# main.net
KiCad netlist of a schematic drawn in Altium Designer
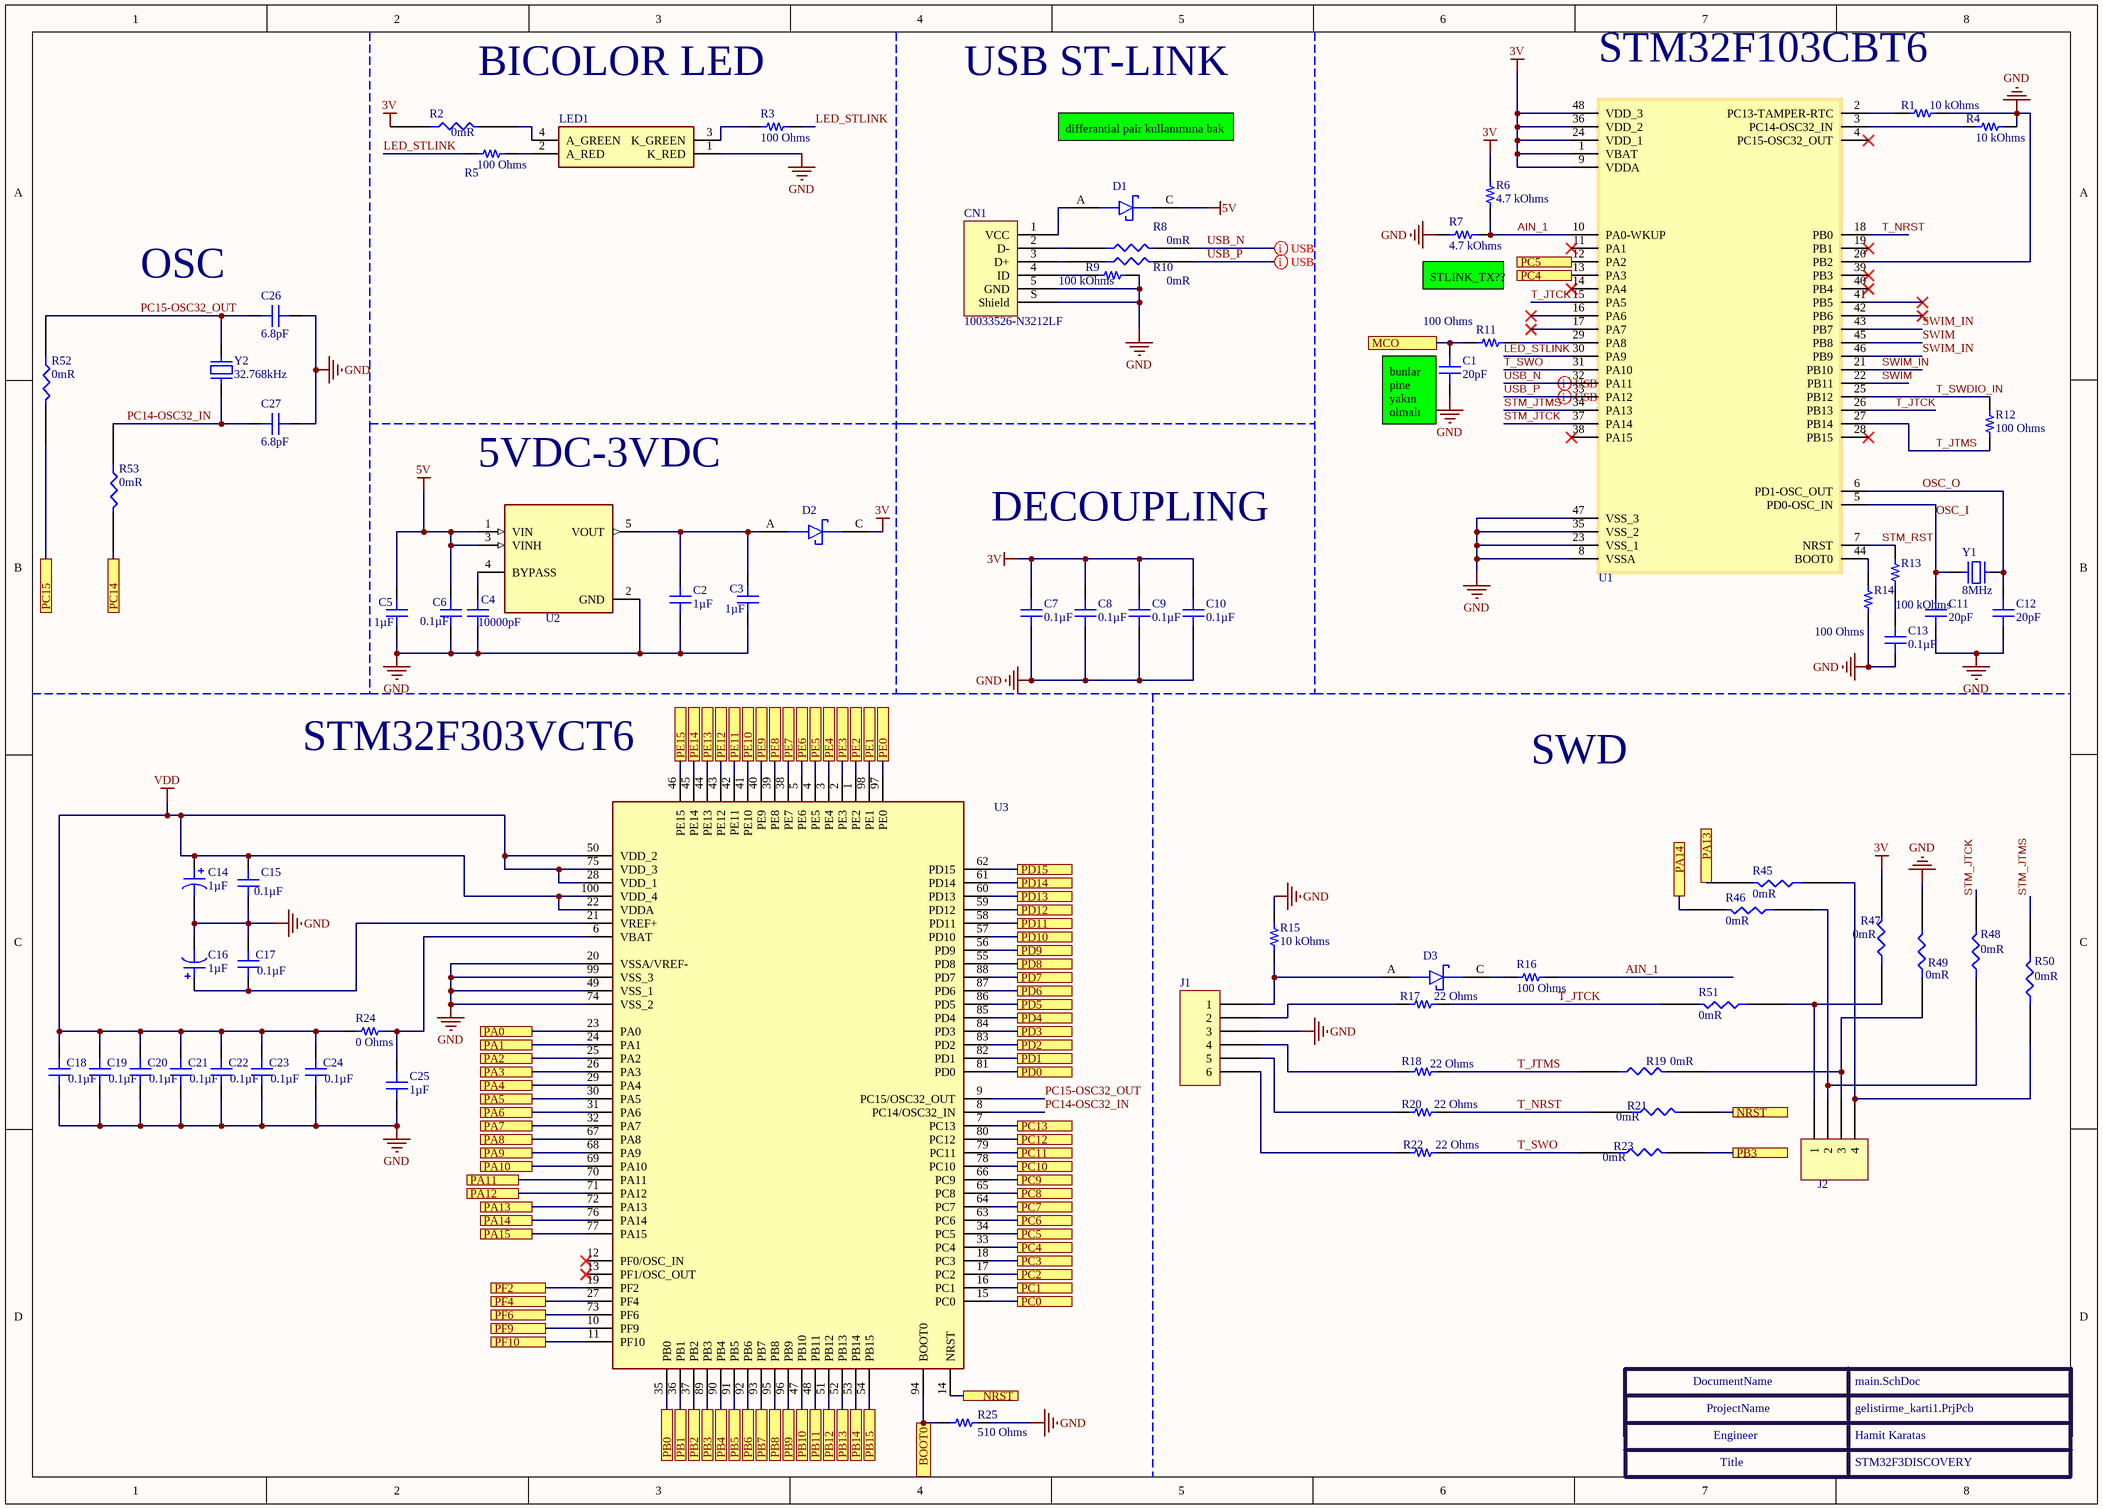
[diagram p0: main.SchDoc]

(export (version "E")
  (design (tool "Eeschema 10.0.6"))
  (components
    (comp (ref "C1")
      (value "20pF")
      (footprint "CAP 0603_1608")
      (description "CAP CER 20PF 250V 0603")
      (fields (field (name "PART NUMBER") "SQCSVA200JAT1A") (field (name "MANUFACTURER") "AVX Corporation"))
      (libsource (lib "Celestial Altium Library - altium_library (4)") (part "Capacitor"))
    )
    (comp (ref "C2")
      (value "1µF")
      (footprint "CAP 0603_1608")
      (description "CAP CER 0603 1UF 16V X7R 10%")
      (fields (field (name "PART NUMBER") "C0603C105K4RACAUTO") (field (name "MANUFACTURER") "KEMET"))
      (libsource (lib "Celestial Altium Library - altium_library (4)") (part "Capacitor"))
    )
    (comp (ref "C3")
      (value "1µF")
      (footprint "CAP 0603_1608")
      (description "CAP CER 0603 1UF 16V X7R 10%")
      (fields (field (name "PART NUMBER") "C0603C105K4RACAUTO") (field (name "MANUFACTURER") "KEMET"))
      (libsource (lib "Celestial Altium Library - altium_library (4)") (part "Capacitor"))
    )
    (comp (ref "C4")
      (value "10000pF")
      (footprint "CAP 0603_1608")
      (description "CAP CER 0603 10NF 100V X7R")
      (fields (field (name "PART NUMBER") "C0603X103K1RAC3316") (field (name "MANUFACTURER") "KEMET"))
      (libsource (lib "Celestial Altium Library - altium_library (4)") (part "Capacitor"))
    )
    (comp (ref "C5")
      (value "1µF")
      (footprint "CAP 0603_1608")
      (description "CAP CER 0603 1UF 16V X7R 10%")
      (fields (field (name "PART NUMBER") "C0603C105K4RACAUTO") (field (name "MANUFACTURER") "KEMET"))
      (libsource (lib "Celestial Altium Library - altium_library (4)") (part "Capacitor"))
    )
    (comp (ref "C6")
      (value "0.1µF")
      (footprint "CAP 0603_1608")
      (description "CAP CER 0.1UF 50V X7R 0603")
      (fields (field (name "PART NUMBER") "C0603C104K5RAC7411") (field (name "MANUFACTURER") "KEMET"))
      (libsource (lib "Celestial Altium Library - altium_library (4)") (part "Capacitor"))
    )
    (comp (ref "C7")
      (value "0.1µF")
      (footprint "CAP 0603_1608")
      (description "CAP CER 0.1UF 50V X7R 0603")
      (fields (field (name "PART NUMBER") "C0603C104K5RAC7411") (field (name "MANUFACTURER") "KEMET"))
      (libsource (lib "Celestial Altium Library - altium_library (4)") (part "Capacitor"))
    )
    (comp (ref "C8")
      (value "0.1µF")
      (footprint "CAP 0603_1608")
      (description "CAP CER 0.1UF 50V X7R 0603")
      (fields (field (name "PART NUMBER") "C0603C104K5RAC7411") (field (name "MANUFACTURER") "KEMET"))
      (libsource (lib "Celestial Altium Library - altium_library (4)") (part "Capacitor"))
    )
    (comp (ref "C9")
      (value "0.1µF")
      (footprint "CAP 0603_1608")
      (description "CAP CER 0.1UF 50V X7R 0603")
      (fields (field (name "PART NUMBER") "C0603C104K5RAC7411") (field (name "MANUFACTURER") "KEMET"))
      (libsource (lib "Celestial Altium Library - altium_library (4)") (part "Capacitor"))
    )
    (comp (ref "C10")
      (value "0.1µF")
      (footprint "CAP 0603_1608")
      (description "CAP CER 0.1UF 50V X7R 0603")
      (fields (field (name "PART NUMBER") "C0603C104K5RAC7411") (field (name "MANUFACTURER") "KEMET"))
      (libsource (lib "Celestial Altium Library - altium_library (4)") (part "Capacitor"))
    )
    (comp (ref "C11")
      (value "20pF")
      (footprint "CAP 0603_1608")
      (description "CAP CER 20PF 250V 0603")
      (fields (field (name "PART NUMBER") "SQCSVA200JAT1A") (field (name "MANUFACTURER") "AVX Corporation"))
      (libsource (lib "Celestial Altium Library - altium_library (4)") (part "Capacitor"))
    )
    (comp (ref "C12")
      (value "20pF")
      (footprint "CAP 0603_1608")
      (description "CAP CER 20PF 250V 0603")
      (fields (field (name "PART NUMBER") "SQCSVA200JAT1A") (field (name "MANUFACTURER") "AVX Corporation"))
      (libsource (lib "Celestial Altium Library - altium_library (4)") (part "Capacitor"))
    )
    (comp (ref "C13")
      (value "0.1µF")
      (footprint "CAP 0603_1608")
      (description "CAP CER 0.1UF 50V X7R 0603")
      (fields (field (name "PART NUMBER") "C0603C104K5RAC7411") (field (name "MANUFACTURER") "KEMET"))
      (libsource (lib "Celestial Altium Library - altium_library (4)") (part "Capacitor"))
    )
    (comp (ref "C14")
      (value "1µF")
      (footprint "CAP ALSMD POLY 4.3MM H5.5MM")
      (description "CAP ALUM 1UF 20% 50V SMD")
      (fields
        (field (name "PART NUMBER") "EEE-1HA010NR")
        (field (name "MANUFACTURER") "Panasonic Electronic Components")
      )
      (libsource (lib "Celestial Altium Library - altium_library (4)") (part "Polarised Capacitor"))
    )
    (comp (ref "C15")
      (value "0.1µF")
      (footprint "CAP 0603_1608")
      (description "CAP CER 0.1UF 50V X7R 0603")
      (fields (field (name "PART NUMBER") "C0603C104K5RAC7411") (field (name "MANUFACTURER") "KEMET"))
      (libsource (lib "Celestial Altium Library - altium_library (4)") (part "Capacitor"))
    )
    (comp (ref "C16")
      (value "1µF")
      (footprint "CAP ALSMD POLY 4.3MM H5.5MM")
      (description "CAP ALUM 1UF 20% 50V SMD")
      (fields
        (field (name "PART NUMBER") "EEE-1HA010NR")
        (field (name "MANUFACTURER") "Panasonic Electronic Components")
      )
      (libsource (lib "Celestial Altium Library - altium_library (4)") (part "Polarised Capacitor"))
    )
    (comp (ref "C17")
      (value "0.1µF")
      (footprint "CAP 0603_1608")
      (description "CAP CER 0.1UF 50V X7R 0603")
      (fields (field (name "PART NUMBER") "C0603C104K5RAC7411") (field (name "MANUFACTURER") "KEMET"))
      (libsource (lib "Celestial Altium Library - altium_library (4)") (part "Capacitor"))
    )
    (comp (ref "C18")
      (value "0.1µF")
      (footprint "CAP 0603_1608")
      (description "CAP CER 0.1UF 50V X7R 0603")
      (fields (field (name "PART NUMBER") "C0603C104K5RAC7411") (field (name "MANUFACTURER") "KEMET"))
      (libsource (lib "Celestial Altium Library - altium_library (4)") (part "Capacitor"))
    )
    (comp (ref "C19")
      (value "0.1µF")
      (footprint "CAP 0603_1608")
      (description "CAP CER 0.1UF 50V X7R 0603")
      (fields (field (name "PART NUMBER") "C0603C104K5RAC7411") (field (name "MANUFACTURER") "KEMET"))
      (libsource (lib "Celestial Altium Library - altium_library (4)") (part "Capacitor"))
    )
    (comp (ref "C20")
      (value "0.1µF")
      (footprint "CAP 0603_1608")
      (description "CAP CER 0.1UF 50V X7R 0603")
      (fields (field (name "PART NUMBER") "C0603C104K5RAC7411") (field (name "MANUFACTURER") "KEMET"))
      (libsource (lib "Celestial Altium Library - altium_library (4)") (part "Capacitor"))
    )
    (comp (ref "C21")
      (value "0.1µF")
      (footprint "CAP 0603_1608")
      (description "CAP CER 0.1UF 50V X7R 0603")
      (fields (field (name "PART NUMBER") "C0603C104K5RAC7411") (field (name "MANUFACTURER") "KEMET"))
      (libsource (lib "Celestial Altium Library - altium_library (4)") (part "Capacitor"))
    )
    (comp (ref "C22")
      (value "0.1µF")
      (footprint "CAP 0603_1608")
      (description "CAP CER 0.1UF 50V X7R 0603")
      (fields (field (name "PART NUMBER") "C0603C104K5RAC7411") (field (name "MANUFACTURER") "KEMET"))
      (libsource (lib "Celestial Altium Library - altium_library (4)") (part "Capacitor"))
    )
    (comp (ref "C23")
      (value "0.1µF")
      (footprint "CAP 0603_1608")
      (description "CAP CER 0.1UF 50V X7R 0603")
      (fields (field (name "PART NUMBER") "C0603C104K5RAC7411") (field (name "MANUFACTURER") "KEMET"))
      (libsource (lib "Celestial Altium Library - altium_library (4)") (part "Capacitor"))
    )
    (comp (ref "C24")
      (value "0.1µF")
      (footprint "CAP 0603_1608")
      (description "CAP CER 0.1UF 50V X7R 0603")
      (fields (field (name "PART NUMBER") "C0603C104K5RAC7411") (field (name "MANUFACTURER") "KEMET"))
      (libsource (lib "Celestial Altium Library - altium_library (4)") (part "Capacitor"))
    )
    (comp (ref "C25")
      (value "1µF")
      (footprint "CAP 0603_1608")
      (description "CAP CER 0603 1UF 16V X7R 10%")
      (fields (field (name "PART NUMBER") "C0603C105K4RACAUTO") (field (name "MANUFACTURER") "KEMET"))
      (libsource (lib "Celestial Altium Library - altium_library (4)") (part "Capacitor"))
    )
    (comp (ref "C26")
      (value "6.8pF")
      (footprint "CAP 0603_1608")
      (description "CAP CER 6.8PF 50V C0G/NP0 0603")
      (fields (field (name "PART NUMBER") "C0603C689J5GACTU") (field (name "MANUFACTURER") "KEMET"))
      (libsource (lib "Celestial Altium Library - altium_library (4)") (part "Capacitor"))
    )
    (comp (ref "C27")
      (value "6.8pF")
      (footprint "CAP 0603_1608")
      (description "CAP CER 6.8PF 50V C0G/NP0 0603")
      (fields (field (name "PART NUMBER") "C0603C689J5GACTU") (field (name "MANUFACTURER") "KEMET"))
      (libsource (lib "Celestial Altium Library - altium_library (4)") (part "Capacitor"))
    )
    (comp (ref "CN1")
      (value "10033526-N3212LF")
      (footprint "FCI USB 10033526-N3212LF")
      (description "CONN RCPT MINI USB B 5POS SMD RA")
      (fields (field (name "MANUFACTURER") "Amphenol ICC (FCI)"))
      (libsource (lib "Celestial Altium Library - altium_library (4)") (part "USB 2.0 Type B Micro"))
    )
    (comp (ref "D1")
      (value "BAT60J")
      (footprint "SOD-323")
      (fields
        (field (name "MANUFACTURER") "STMicroelectronics")
        (field (name "MANUFACTURER PART NUMBER") "BAT60JFILM")
      )
      (libsource (lib "giris_intlib") (part "DIODE SCHOTTKY"))
    )
    (comp (ref "D2")
      (value "BAT60J")
      (footprint "SOD-323")
      (fields
        (field (name "MANUFACTURER") "STMicroelectronics")
        (field (name "MANUFACTURER PART NUMBER") "BAT60JFILM")
      )
      (libsource (lib "giris_intlib") (part "DIODE SCHOTTKY"))
    )
    (comp (ref "D3")
      (value "BAT60J")
      (footprint "SOD-323")
      (fields
        (field (name "MANUFACTURER") "STMicroelectronics")
        (field (name "MANUFACTURER PART NUMBER") "BAT60JFILM")
      )
      (libsource (lib "giris_intlib") (part "DIODE SCHOTTKY"))
    )
    (comp (ref "J1")
      (value "B6B-PH-K(LF)(SN)")
      (footprint "JST B6B-PH-K")
      (description "CONN HEADER VERT 6POS 2MM")
      (fields (field (name "MANUFACTURER") "JST Sales America Inc."))
      (libsource (lib "Celestial Altium Library - altium_library (4)") (part "6 Pin"))
    )
    (comp (ref "J2")
      (value "B4B-PH-K-S(LF)(SN)")
      (footprint "JST B4B-PH-K")
      (description "CONN HEADER VERT 4POS 2MM")
      (fields (field (name "MANUFACTURER") "JST Sales America Inc."))
      (libsource (lib "Celestial Altium Library - altium_library (4)") (part "4 Pin"))
    )
    (comp (ref "LED1")
      (value "IN-S85DATRG")
      (footprint "altium_giris:INS85DATRG")
      (description "LED")
      (fields (field (name "MOUSER PART NUMBER") "743-IN-S85DATRG"))
      (libsource (lib "*") (part "IN-S85DATRG"))
    )
    (comp (ref "R1")
      (value "10 kOhms")
      (footprint "RES 0603_1608")
      (description "RES SMD 10K OHM 0.5% 1/10W 0603")
      (fields (field (name "PART NUMBER") "RT0603DRD0710KL") (field (name "MANUFACTURER") "Yageo"))
      (libsource (lib "Celestial Altium Library - altium_library (4)") (part "Resistor"))
    )
    (comp (ref "R2")
      (value "RC0603JR-070RL")
      (footprint "RES_0603")
      (description "RES SMD 0 OHM JUMPER 1/10W 0603")
      (fields
        (field (name "MANUFACTURER") "Yageo")
        (field (name "TOLERANCE") "1%")
        (field (name "RESISTANCE") "0mR")
      )
      (libsource (lib "giris_intlib") (part "Res 0 ohm 0603"))
    )
    (comp (ref "R3")
      (value "100 Ohms")
      (footprint "RES 0603_1608")
      (description "RES 100 OHM 0.1% 1/16W 0603")
      (fields
        (field (name "PART NUMBER") "RNCS0603BKE100R")
        (field (name "MANUFACTURER") "Stackpole Electronics Inc")
      )
      (libsource (lib "Celestial Altium Library - altium_library (4)") (part "Resistor"))
    )
    (comp (ref "R4")
      (value "10 kOhms")
      (footprint "RES 0603_1608")
      (description "RES SMD 10K OHM 0.5% 1/10W 0603")
      (fields (field (name "PART NUMBER") "RT0603DRD0710KL") (field (name "MANUFACTURER") "Yageo"))
      (libsource (lib "Celestial Altium Library - altium_library (4)") (part "Resistor"))
    )
    (comp (ref "R5")
      (value "100 Ohms")
      (footprint "RES 0603_1608")
      (description "RES 100 OHM 0.1% 1/16W 0603")
      (fields
        (field (name "PART NUMBER") "RNCS0603BKE100R")
        (field (name "MANUFACTURER") "Stackpole Electronics Inc")
      )
      (libsource (lib "Celestial Altium Library - altium_library (4)") (part "Resistor"))
    )
    (comp (ref "R6")
      (value "4.7 kOhms")
      (footprint "RES 0603_1608")
      (description "RES SMD 4.7K OHM 1% 1/10W 0603")
      (fields (field (name "PART NUMBER") "RT0603FRE074K7L") (field (name "MANUFACTURER") "Yageo"))
      (libsource (lib "Celestial Altium Library - altium_library (4)") (part "Resistor"))
    )
    (comp (ref "R7")
      (value "4.7 kOhms")
      (footprint "RES 0603_1608")
      (description "RES SMD 4.7K OHM 1% 1/10W 0603")
      (fields (field (name "PART NUMBER") "RT0603FRE074K7L") (field (name "MANUFACTURER") "Yageo"))
      (libsource (lib "Celestial Altium Library - altium_library (4)") (part "Resistor"))
    )
    (comp (ref "R8")
      (value "RC0603JR-070RL")
      (footprint "RES_0603")
      (description "RES SMD 0 OHM JUMPER 1/10W 0603")
      (fields
        (field (name "MANUFACTURER") "Yageo")
        (field (name "TOLERANCE") "1%")
        (field (name "RESISTANCE") "0mR")
      )
      (libsource (lib "giris_intlib") (part "Res 0 ohm 0603"))
    )
    (comp (ref "R9")
      (value "100 kOhms")
      (footprint "RES 0603_1608")
      (description "RES SMD 100K OHM 0.5% 1/10W 0603")
      (fields (field (name "PART NUMBER") "AT0603DRD07100KL") (field (name "MANUFACTURER") "Yageo"))
      (libsource (lib "Celestial Altium Library - altium_library (4)") (part "Resistor"))
    )
    (comp (ref "R10")
      (value "RC0603JR-070RL")
      (footprint "RES_0603")
      (description "RES SMD 0 OHM JUMPER 1/10W 0603")
      (fields
        (field (name "MANUFACTURER") "Yageo")
        (field (name "TOLERANCE") "1%")
        (field (name "RESISTANCE") "0mR")
      )
      (libsource (lib "giris_intlib") (part "Res 0 ohm 0603"))
    )
    (comp (ref "R11")
      (value "100 Ohms")
      (footprint "RES 0603_1608")
      (description "RES 100 OHM 0.1% 1/16W 0603")
      (fields
        (field (name "PART NUMBER") "RNCS0603BKE100R")
        (field (name "MANUFACTURER") "Stackpole Electronics Inc")
      )
      (libsource (lib "Celestial Altium Library - altium_library (4)") (part "Resistor"))
    )
    (comp (ref "R12")
      (value "100 Ohms")
      (footprint "RES 0603_1608")
      (description "RES 100 OHM 0.1% 1/16W 0603")
      (fields
        (field (name "PART NUMBER") "RNCS0603BKE100R")
        (field (name "MANUFACTURER") "Stackpole Electronics Inc")
      )
      (libsource (lib "Celestial Altium Library - altium_library (4)") (part "Resistor"))
    )
    (comp (ref "R13")
      (value "100 kOhms")
      (footprint "RES 0603_1608")
      (description "RES SMD 100K OHM 0.5% 1/10W 0603")
      (fields (field (name "PART NUMBER") "AT0603DRD07100KL") (field (name "MANUFACTURER") "Yageo"))
      (libsource (lib "Celestial Altium Library - altium_library (4)") (part "Resistor"))
    )
    (comp (ref "R14")
      (value "100 Ohms")
      (footprint "RES 0603_1608")
      (description "RES 100 OHM 0.1% 1/16W 0603")
      (fields
        (field (name "PART NUMBER") "RNCS0603BKE100R")
        (field (name "MANUFACTURER") "Stackpole Electronics Inc")
      )
      (libsource (lib "Celestial Altium Library - altium_library (4)") (part "Resistor"))
    )
    (comp (ref "R15")
      (value "10 kOhms")
      (footprint "RES 0603_1608")
      (description "RES SMD 10K OHM 0.5% 1/10W 0603")
      (fields (field (name "PART NUMBER") "RT0603DRD0710KL") (field (name "MANUFACTURER") "Yageo"))
      (libsource (lib "Celestial Altium Library - altium_library (4)") (part "Resistor"))
    )
    (comp (ref "R16")
      (value "100 Ohms")
      (footprint "RES 0603_1608")
      (description "RES 100 OHM 0.1% 1/16W 0603")
      (fields
        (field (name "PART NUMBER") "RNCS0603BKE100R")
        (field (name "MANUFACTURER") "Stackpole Electronics Inc")
      )
      (libsource (lib "Celestial Altium Library - altium_library (4)") (part "Resistor"))
    )
    (comp (ref "R17")
      (value "22 Ohms")
      (footprint "RES 0603_1608")
      (description "RES 22 OHM 5% 1/8W 0603")
      (fields
        (field (name "PART NUMBER") "RK73B1JTTD220J")
        (field (name "MANUFACTURER") "KOA Speer Electronics, Inc.")
      )
      (libsource (lib "Celestial Altium Library - altium_library (4)") (part "Resistor"))
    )
    (comp (ref "R18")
      (value "22 Ohms")
      (footprint "RES 0603_1608")
      (description "RES 22 OHM 5% 1/8W 0603")
      (fields
        (field (name "PART NUMBER") "RK73B1JTTD220J")
        (field (name "MANUFACTURER") "KOA Speer Electronics, Inc.")
      )
      (libsource (lib "Celestial Altium Library - altium_library (4)") (part "Resistor"))
    )
    (comp (ref "R19")
      (value "RC0603JR-070RL")
      (footprint "RES_0603")
      (description "RES SMD 0 OHM JUMPER 1/10W 0603")
      (fields
        (field (name "MANUFACTURER") "Yageo")
        (field (name "TOLERANCE") "1%")
        (field (name "RESISTANCE") "0mR")
      )
      (libsource (lib "giris_intlib") (part "Res 0 ohm 0603"))
    )
    (comp (ref "R20")
      (value "22 Ohms")
      (footprint "RES 0603_1608")
      (description "RES 22 OHM 5% 1/8W 0603")
      (fields
        (field (name "PART NUMBER") "RK73B1JTTD220J")
        (field (name "MANUFACTURER") "KOA Speer Electronics, Inc.")
      )
      (libsource (lib "Celestial Altium Library - altium_library (4)") (part "Resistor"))
    )
    (comp (ref "R21")
      (value "RC0603JR-070RL")
      (footprint "RES_0603")
      (description "RES SMD 0 OHM JUMPER 1/10W 0603")
      (fields
        (field (name "MANUFACTURER") "Yageo")
        (field (name "TOLERANCE") "1%")
        (field (name "RESISTANCE") "0mR")
      )
      (libsource (lib "giris_intlib") (part "Res 0 ohm 0603"))
    )
    (comp (ref "R22")
      (value "22 Ohms")
      (footprint "RES 0603_1608")
      (description "RES 22 OHM 5% 1/8W 0603")
      (fields
        (field (name "PART NUMBER") "RK73B1JTTD220J")
        (field (name "MANUFACTURER") "KOA Speer Electronics, Inc.")
      )
      (libsource (lib "Celestial Altium Library - altium_library (4)") (part "Resistor"))
    )
    (comp (ref "R23")
      (value "RC0603JR-070RL")
      (footprint "RES_0603")
      (description "RES SMD 0 OHM JUMPER 1/10W 0603")
      (fields
        (field (name "MANUFACTURER") "Yageo")
        (field (name "TOLERANCE") "1%")
        (field (name "RESISTANCE") "0mR")
      )
      (libsource (lib "giris_intlib") (part "Res 0 ohm 0603"))
    )
    (comp (ref "R24")
      (value "0 Ohms")
      (footprint "RES 0603_1608")
      (description "RES SMD 0 OHM JUMPER 1/10W 0603")
      (fields (field (name "PART NUMBER") "RC0603FR-070RL") (field (name "MANUFACTURER") "Yageo"))
      (libsource (lib "Celestial Altium Library - altium_library (4)") (part "Resistor"))
    )
    (comp (ref "R25")
      (value "510 Ohms")
      (footprint "RES 0603_1608")
      (description "RES 510 OHM 0.1% 1/10W 0603")
      (fields
        (field (name "PART NUMBER") "RN73R1JTTD5100B25")
        (field (name "MANUFACTURER") "KOA Speer Electronics, Inc.")
      )
      (libsource (lib "Celestial Altium Library - altium_library (4)") (part "Resistor"))
    )
    (comp (ref "R45")
      (value "RC0603JR-070RL")
      (footprint "RES_0603")
      (description "RES SMD 0 OHM JUMPER 1/10W 0603")
      (fields
        (field (name "MANUFACTURER") "Yageo")
        (field (name "TOLERANCE") "1%")
        (field (name "RESISTANCE") "0mR")
      )
      (libsource (lib "giris_intlib") (part "Res 0 ohm 0603"))
    )
    (comp (ref "R46")
      (value "RC0603JR-070RL")
      (footprint "RES_0603")
      (description "RES SMD 0 OHM JUMPER 1/10W 0603")
      (fields
        (field (name "MANUFACTURER") "Yageo")
        (field (name "TOLERANCE") "1%")
        (field (name "RESISTANCE") "0mR")
      )
      (libsource (lib "giris_intlib") (part "Res 0 ohm 0603"))
    )
    (comp (ref "R47")
      (value "RC0603JR-070RL")
      (footprint "RES_0603")
      (description "RES SMD 0 OHM JUMPER 1/10W 0603")
      (fields
        (field (name "MANUFACTURER") "Yageo")
        (field (name "TOLERANCE") "1%")
        (field (name "RESISTANCE") "0mR")
      )
      (libsource (lib "giris_intlib") (part "Res 0 ohm 0603"))
    )
    (comp (ref "R48")
      (value "RC0603JR-070RL")
      (footprint "RES_0603")
      (description "RES SMD 0 OHM JUMPER 1/10W 0603")
      (fields
        (field (name "MANUFACTURER") "Yageo")
        (field (name "TOLERANCE") "1%")
        (field (name "RESISTANCE") "0mR")
      )
      (libsource (lib "giris_intlib") (part "Res 0 ohm 0603"))
    )
    (comp (ref "R49")
      (value "RC0603JR-070RL")
      (footprint "RES_0603")
      (description "RES SMD 0 OHM JUMPER 1/10W 0603")
      (fields
        (field (name "MANUFACTURER") "Yageo")
        (field (name "TOLERANCE") "1%")
        (field (name "RESISTANCE") "0mR")
      )
      (libsource (lib "giris_intlib") (part "Res 0 ohm 0603"))
    )
    (comp (ref "R50")
      (value "RC0603JR-070RL")
      (footprint "RES_0603")
      (description "RES SMD 0 OHM JUMPER 1/10W 0603")
      (fields
        (field (name "MANUFACTURER") "Yageo")
        (field (name "TOLERANCE") "1%")
        (field (name "RESISTANCE") "0mR")
      )
      (libsource (lib "giris_intlib") (part "Res 0 ohm 0603"))
    )
    (comp (ref "R51")
      (value "RC0603JR-070RL")
      (footprint "RES_0603")
      (description "RES SMD 0 OHM JUMPER 1/10W 0603")
      (fields
        (field (name "MANUFACTURER") "Yageo")
        (field (name "TOLERANCE") "1%")
        (field (name "RESISTANCE") "0mR")
      )
      (libsource (lib "giris_intlib") (part "Res 0 ohm 0603"))
    )
    (comp (ref "R52")
      (value "RC0603JR-070RL")
      (footprint "RES_0603")
      (description "RES SMD 0 OHM JUMPER 1/10W 0603")
      (fields
        (field (name "MANUFACTURER") "Yageo")
        (field (name "TOLERANCE") "1%")
        (field (name "RESISTANCE") "0mR")
      )
      (libsource (lib "giris_intlib") (part "Res 0 ohm 0603"))
    )
    (comp (ref "R53")
      (value "RC0603JR-070RL")
      (footprint "RES_0603")
      (description "RES SMD 0 OHM JUMPER 1/10W 0603")
      (fields
        (field (name "MANUFACTURER") "Yageo")
        (field (name "TOLERANCE") "1%")
        (field (name "RESISTANCE") "0mR")
      )
      (libsource (lib "giris_intlib") (part "Res 0 ohm 0603"))
    )
    (comp (ref "U1")
      (value "IC MCU 32BIT 128KB FLASH 48LQFP")
      (footprint "STM32F103CBT6")
      (description "MCU 32-bit STM32F1 ARM Cortex M3 RISC 128KB Flash 2.5V/3.3V 48-Pin LQFP Tray")
      (fields
        (field (name "MANUFACTURER") "STMicroelectronics")
        (field (name "MANUFACTURER PART NUMBER") "STM32F103CBT6")
      )
      (libsource (lib "giris_intlib") (part "STM32F103CBT6"))
    )
    (comp (ref "U2")
      (value "LD3985M33R")
      (footprint "SOT23-T")
      (description "LDO Regulator Pos 3.3V 0.55A 5-Pin SOT-23 T/R")
      (fields (field (name "MANUFACTURER") "STMicroelectronics"))
      (libsource (lib "giris_intlib") (part "voltage regulator_3v3 150mA"))
    )
    (comp (ref "U3")
      (value "STM32F303VCT6")
      (footprint "LQFP-100")
      (description "ARM Microcontrollers - MCU 32-Bit ARM Cortex M4 72MHz 256kB MCU FPU")
      (fields (field (name "MANUFACTURER") "STMicroelectronics"))
      (libsource (lib "giris_intlib") (part "STM32F303VCT6"))
    )
    (comp (ref "Y1")
      (value "8MHz")
      (footprint "ABRACON ABLS")
      (description "CRYSTAL 8.0000MHZ 20PF SMD")
      (fields
        (field (name "PART NUMBER") "ABLS-8.000MHZ-20-D-3-H-T")
        (field (name "MANUFACTURER") "Abracon LLC")
      )
      (libsource (lib "Celestial Altium Library - altium_library (4)") (part "Abracon Crystal ABLS"))
    )
    (comp (ref "Y2")
      (value "32.768kHz")
      (footprint "ABRACON ABS07")
      (description "CRYSTAL 32.7680KHZ 6PF SMD")
      (fields
        (field (name "PART NUMBER") "ABS07-32.768KHZ-6-4-T")
        (field (name "MANUFACTURER") "Abracon LLC")
      )
      (libsource (lib "Celestial Altium Library - altium_library (4)") (part "Abracon Crystal ABS07"))
    )
  )
  (nets
    (net (code "1") (name "/AIN_1") (class "Default")
      (node (ref "R16") (pin "2") (pinfunction "2_2") (pintype "passive"))
      (node (ref "R6") (pin "2") (pinfunction "2_2") (pintype "passive"))
      (node (ref "R7") (pin "1") (pinfunction "1_1") (pintype "passive"))
      (node (ref "U1") (pin "10") (pinfunction "PA0-WKUP_10") (pintype "passive"))
    )
    (net (code "2") (name "/BOOT0") (class "Default")
      (node (ref "R25") (pin "1") (pinfunction "1_1") (pintype "passive"))
      (node (ref "U3") (pin "94") (pinfunction "BOOT0_94") (pintype "passive"))
    )
    (net (code "3") (name "/LED_STLINK") (class "Default")
      (node (ref "R3") (pin "2") (pinfunction "2_2") (pintype "passive"))
      (node (ref "R5") (pin "1") (pinfunction "1_1") (pintype "passive"))
      (node (ref "U1") (pin "30") (pinfunction "PA9_30") (pintype "passive"))
    )
    (net (code "4") (name "/MCO") (class "Default")
      (node (ref "C1") (pin "2") (pinfunction "2_2") (pintype "passive"))
      (node (ref "R11") (pin "2") (pinfunction "2_2") (pintype "passive"))
    )
    (net (code "5") (name "/NRST") (class "Default")
      (node (ref "R21") (pin "2") (pinfunction "2_2") (pintype "passive"))
      (node (ref "U3") (pin "14") (pinfunction "NRST_14") (pintype "passive"))
    )
    (net (code "6") (name "/OSC_I") (class "Default")
      (node (ref "C11") (pin "2") (pinfunction "2_2") (pintype "passive"))
      (node (ref "U1") (pin "5") (pinfunction "PD0-OSC_IN_5") (pintype "passive"))
      (node (ref "Y1") (pin "2") (pinfunction "2_2") (pintype "passive"))
    )
    (net (code "7") (name "/OSC_O") (class "Default")
      (node (ref "C12") (pin "2") (pinfunction "2_2") (pintype "passive"))
      (node (ref "U1") (pin "6") (pinfunction "PD1-OSC_OUT_6") (pintype "passive"))
      (node (ref "Y1") (pin "1") (pinfunction "1_1") (pintype "passive"))
    )
    (net (code "8") (name "/PA0") (class "Default")
      (node (ref "U3") (pin "23") (pinfunction "PA0_23") (pintype "passive"))
    )
    (net (code "9") (name "/PA1") (class "Default")
      (node (ref "U3") (pin "24") (pinfunction "PA1_24") (pintype "passive"))
    )
    (net (code "10") (name "/PA2") (class "Default")
      (node (ref "U3") (pin "25") (pinfunction "PA2_25") (pintype "passive"))
    )
    (net (code "11") (name "/PA3") (class "Default")
      (node (ref "U3") (pin "26") (pinfunction "PA3_26") (pintype "passive"))
    )
    (net (code "12") (name "/PA4") (class "Default")
      (node (ref "U3") (pin "29") (pinfunction "PA4_29") (pintype "passive"))
    )
    (net (code "13") (name "/PA5") (class "Default")
      (node (ref "U3") (pin "30") (pinfunction "PA5_30") (pintype "passive"))
    )
    (net (code "14") (name "/PA6") (class "Default")
      (node (ref "U3") (pin "31") (pinfunction "PA6_31") (pintype "passive"))
    )
    (net (code "15") (name "/PA7") (class "Default")
      (node (ref "U3") (pin "32") (pinfunction "PA7_32") (pintype "passive"))
    )
    (net (code "16") (name "/PA8") (class "Default")
      (node (ref "U3") (pin "67") (pinfunction "PA8_67") (pintype "passive"))
    )
    (net (code "17") (name "/PA9") (class "Default")
      (node (ref "U3") (pin "68") (pinfunction "PA9_68") (pintype "passive"))
    )
    (net (code "18") (name "/PA10") (class "Default")
      (node (ref "U3") (pin "69") (pinfunction "PA10_69") (pintype "passive"))
    )
    (net (code "19") (name "/PA11") (class "Default")
      (node (ref "U3") (pin "70") (pinfunction "PA11_70") (pintype "passive"))
    )
    (net (code "20") (name "/PA12") (class "Default")
      (node (ref "U3") (pin "71") (pinfunction "PA12_71") (pintype "passive"))
    )
    (net (code "21") (name "/PA13") (class "Default")
      (node (ref "R45") (pin "2") (pinfunction "2_2") (pintype "passive"))
      (node (ref "U3") (pin "72") (pinfunction "PA13_72") (pintype "passive"))
    )
    (net (code "22") (name "/PA14") (class "Default")
      (node (ref "R46") (pin "2") (pinfunction "2_2") (pintype "passive"))
      (node (ref "U3") (pin "76") (pinfunction "PA14_76") (pintype "passive"))
    )
    (net (code "23") (name "/PA15") (class "Default")
      (node (ref "U3") (pin "77") (pinfunction "PA15_77") (pintype "passive"))
    )
    (net (code "24") (name "/PB0") (class "Default")
      (node (ref "U3") (pin "35") (pinfunction "PB0_35") (pintype "passive"))
    )
    (net (code "25") (name "/PB1") (class "Default")
      (node (ref "U3") (pin "36") (pinfunction "PB1_36") (pintype "passive"))
    )
    (net (code "26") (name "/PB2") (class "Default")
      (node (ref "U3") (pin "37") (pinfunction "PB2_37") (pintype "passive"))
    )
    (net (code "27") (name "/PB3") (class "Default")
      (node (ref "R23") (pin "2") (pinfunction "2_2") (pintype "passive"))
      (node (ref "U3") (pin "89") (pinfunction "PB3_89") (pintype "passive"))
    )
    (net (code "28") (name "/PB4") (class "Default")
      (node (ref "U3") (pin "90") (pinfunction "PB4_90") (pintype "passive"))
    )
    (net (code "29") (name "/PB5") (class "Default")
      (node (ref "U3") (pin "91") (pinfunction "PB5_91") (pintype "passive"))
    )
    (net (code "30") (name "/PB6") (class "Default")
      (node (ref "U3") (pin "92") (pinfunction "PB6_92") (pintype "passive"))
    )
    (net (code "31") (name "/PB7") (class "Default")
      (node (ref "U3") (pin "93") (pinfunction "PB7_93") (pintype "passive"))
    )
    (net (code "32") (name "/PB8") (class "Default")
      (node (ref "U3") (pin "95") (pinfunction "PB8_95") (pintype "passive"))
    )
    (net (code "33") (name "/PB9") (class "Default")
      (node (ref "U3") (pin "96") (pinfunction "PB9_96") (pintype "passive"))
    )
    (net (code "34") (name "/PB10") (class "Default")
      (node (ref "U3") (pin "47") (pinfunction "PB10_47") (pintype "passive"))
    )
    (net (code "35") (name "/PB11") (class "Default")
      (node (ref "U3") (pin "48") (pinfunction "PB11_48") (pintype "passive"))
    )
    (net (code "36") (name "/PB12") (class "Default")
      (node (ref "U3") (pin "51") (pinfunction "PB12_51") (pintype "passive"))
    )
    (net (code "37") (name "/PB13") (class "Default")
      (node (ref "U3") (pin "52") (pinfunction "PB13_52") (pintype "passive"))
    )
    (net (code "38") (name "/PB14") (class "Default")
      (node (ref "U3") (pin "53") (pinfunction "PB14_53") (pintype "passive"))
    )
    (net (code "39") (name "/PB15") (class "Default")
      (node (ref "U3") (pin "54") (pinfunction "PB15_54") (pintype "passive"))
    )
    (net (code "40") (name "/PC0") (class "Default")
      (node (ref "U3") (pin "15") (pinfunction "PC0_15") (pintype "passive"))
    )
    (net (code "41") (name "/PC1") (class "Default")
      (node (ref "U3") (pin "16") (pinfunction "PC1_16") (pintype "passive"))
    )
    (net (code "42") (name "/PC2") (class "Default")
      (node (ref "U3") (pin "17") (pinfunction "PC2_17") (pintype "passive"))
    )
    (net (code "43") (name "/PC3") (class "Default")
      (node (ref "U3") (pin "18") (pinfunction "PC3_18") (pintype "passive"))
    )
    (net (code "44") (name "/PC4") (class "Default")
      (node (ref "U1") (pin "13") (pinfunction "PA3_13") (pintype "passive"))
      (node (ref "U3") (pin "33") (pinfunction "PC4_33") (pintype "passive"))
    )
    (net (code "45") (name "/PC5") (class "Default")
      (node (ref "U1") (pin "12") (pinfunction "PA2_12") (pintype "passive"))
      (node (ref "U3") (pin "34") (pinfunction "PC5_34") (pintype "passive"))
    )
    (net (code "46") (name "/PC6") (class "Default")
      (node (ref "U3") (pin "63") (pinfunction "PC6_63") (pintype "passive"))
    )
    (net (code "47") (name "/PC7") (class "Default")
      (node (ref "U3") (pin "64") (pinfunction "PC7_64") (pintype "passive"))
    )
    (net (code "48") (name "/PC8") (class "Default")
      (node (ref "U3") (pin "65") (pinfunction "PC8_65") (pintype "passive"))
    )
    (net (code "49") (name "/PC9") (class "Default")
      (node (ref "U3") (pin "66") (pinfunction "PC9_66") (pintype "passive"))
    )
    (net (code "50") (name "/PC10") (class "Default")
      (node (ref "U3") (pin "78") (pinfunction "PC10_78") (pintype "passive"))
    )
    (net (code "51") (name "/PC11") (class "Default")
      (node (ref "U3") (pin "79") (pinfunction "PC11_79") (pintype "passive"))
    )
    (net (code "52") (name "/PC12") (class "Default")
      (node (ref "U3") (pin "80") (pinfunction "PC12_80") (pintype "passive"))
    )
    (net (code "53") (name "/PC13") (class "Default")
      (node (ref "U3") (pin "7") (pinfunction "PC13_7") (pintype "passive"))
    )
    (net (code "54") (name "/PC14") (class "Default")
      (node (ref "R53") (pin "2") (pinfunction "2_2") (pintype "passive"))
    )
    (net (code "55") (name "/PC14-OSC32_IN") (class "Default")
      (node (ref "C27") (pin "2") (pinfunction "2_2") (pintype "passive"))
      (node (ref "R53") (pin "1") (pinfunction "1_1") (pintype "passive"))
      (node (ref "U3") (pin "8") (pinfunction "PC14/OSC32_IN_8") (pintype "passive"))
      (node (ref "Y2") (pin "1") (pinfunction "1_1") (pintype "passive"))
    )
    (net (code "56") (name "/PC15") (class "Default")
      (node (ref "R52") (pin "2") (pinfunction "2_2") (pintype "passive"))
    )
    (net (code "57") (name "/PC15-OSC32_OUT") (class "Default")
      (node (ref "C26") (pin "2") (pinfunction "2_2") (pintype "passive"))
      (node (ref "R52") (pin "1") (pinfunction "1_1") (pintype "passive"))
      (node (ref "U3") (pin "9") (pinfunction "PC15/OSC32_OUT_9") (pintype "passive"))
      (node (ref "Y2") (pin "2") (pinfunction "2_2") (pintype "passive"))
    )
    (net (code "58") (name "/PD0") (class "Default")
      (node (ref "U3") (pin "81") (pinfunction "PD0_81") (pintype "passive"))
    )
    (net (code "59") (name "/PD1") (class "Default")
      (node (ref "U3") (pin "82") (pinfunction "PD1_82") (pintype "passive"))
    )
    (net (code "60") (name "/PD2") (class "Default")
      (node (ref "U3") (pin "83") (pinfunction "PD2_83") (pintype "passive"))
    )
    (net (code "61") (name "/PD3") (class "Default")
      (node (ref "U3") (pin "84") (pinfunction "PD3_84") (pintype "passive"))
    )
    (net (code "62") (name "/PD4") (class "Default")
      (node (ref "U3") (pin "85") (pinfunction "PD4_85") (pintype "passive"))
    )
    (net (code "63") (name "/PD5") (class "Default")
      (node (ref "U3") (pin "86") (pinfunction "PD5_86") (pintype "passive"))
    )
    (net (code "64") (name "/PD6") (class "Default")
      (node (ref "U3") (pin "87") (pinfunction "PD6_87") (pintype "passive"))
    )
    (net (code "65") (name "/PD7") (class "Default")
      (node (ref "U3") (pin "88") (pinfunction "PD7_88") (pintype "passive"))
    )
    (net (code "66") (name "/PD8") (class "Default")
      (node (ref "U3") (pin "55") (pinfunction "PD8_55") (pintype "passive"))
    )
    (net (code "67") (name "/PD9") (class "Default")
      (node (ref "U3") (pin "56") (pinfunction "PD9_56") (pintype "passive"))
    )
    (net (code "68") (name "/PD10") (class "Default")
      (node (ref "U3") (pin "57") (pinfunction "PD10_57") (pintype "passive"))
    )
    (net (code "69") (name "/PD11") (class "Default")
      (node (ref "U3") (pin "58") (pinfunction "PD11_58") (pintype "passive"))
    )
    (net (code "70") (name "/PD12") (class "Default")
      (node (ref "U3") (pin "59") (pinfunction "PD12_59") (pintype "passive"))
    )
    (net (code "71") (name "/PD13") (class "Default")
      (node (ref "U3") (pin "60") (pinfunction "PD13_60") (pintype "passive"))
    )
    (net (code "72") (name "/PD14") (class "Default")
      (node (ref "U3") (pin "61") (pinfunction "PD14_61") (pintype "passive"))
    )
    (net (code "73") (name "/PD15") (class "Default")
      (node (ref "U3") (pin "62") (pinfunction "PD15_62") (pintype "passive"))
    )
    (net (code "74") (name "/PE0") (class "Default")
      (node (ref "U3") (pin "97") (pinfunction "PE0_97") (pintype "passive"))
    )
    (net (code "75") (name "/PE1") (class "Default")
      (node (ref "U3") (pin "98") (pinfunction "PE1_98") (pintype "passive"))
    )
    (net (code "76") (name "/PE2") (class "Default")
      (node (ref "U3") (pin "1") (pinfunction "PE2_1") (pintype "passive"))
    )
    (net (code "77") (name "/PE3") (class "Default")
      (node (ref "U3") (pin "2") (pinfunction "PE3_2") (pintype "passive"))
    )
    (net (code "78") (name "/PE4") (class "Default")
      (node (ref "U3") (pin "3") (pinfunction "PE4_3") (pintype "passive"))
    )
    (net (code "79") (name "/PE5") (class "Default")
      (node (ref "U3") (pin "4") (pinfunction "PE5_4") (pintype "passive"))
    )
    (net (code "80") (name "/PE6") (class "Default")
      (node (ref "U3") (pin "5") (pinfunction "PE6_5") (pintype "passive"))
    )
    (net (code "81") (name "/PE7") (class "Default")
      (node (ref "U3") (pin "38") (pinfunction "PE7_38") (pintype "passive"))
    )
    (net (code "82") (name "/PE8") (class "Default")
      (node (ref "U3") (pin "39") (pinfunction "PE8_39") (pintype "passive"))
    )
    (net (code "83") (name "/PE9") (class "Default")
      (node (ref "U3") (pin "40") (pinfunction "PE9_40") (pintype "passive"))
    )
    (net (code "84") (name "/PE10") (class "Default")
      (node (ref "U3") (pin "41") (pinfunction "PE10_41") (pintype "passive"))
    )
    (net (code "85") (name "/PE11") (class "Default")
      (node (ref "U3") (pin "42") (pinfunction "PE11_42") (pintype "passive"))
    )
    (net (code "86") (name "/PE12") (class "Default")
      (node (ref "U3") (pin "43") (pinfunction "PE12_43") (pintype "passive"))
    )
    (net (code "87") (name "/PE13") (class "Default")
      (node (ref "U3") (pin "44") (pinfunction "PE13_44") (pintype "passive"))
    )
    (net (code "88") (name "/PE14") (class "Default")
      (node (ref "U3") (pin "45") (pinfunction "PE14_45") (pintype "passive"))
    )
    (net (code "89") (name "/PE15") (class "Default")
      (node (ref "U3") (pin "46") (pinfunction "PE15_46") (pintype "passive"))
    )
    (net (code "90") (name "/PF2") (class "Default")
      (node (ref "U3") (pin "19") (pinfunction "PF2_19") (pintype "passive"))
    )
    (net (code "91") (name "/PF4") (class "Default")
      (node (ref "U3") (pin "27") (pinfunction "PF4_27") (pintype "passive"))
    )
    (net (code "92") (name "/PF6") (class "Default")
      (node (ref "U3") (pin "73") (pinfunction "PF6_73") (pintype "passive"))
    )
    (net (code "93") (name "/PF9") (class "Default")
      (node (ref "U3") (pin "10") (pinfunction "PF9_10") (pintype "passive"))
    )
    (net (code "94") (name "/PF10") (class "Default")
      (node (ref "U3") (pin "11") (pinfunction "PF10_11") (pintype "passive"))
    )
    (net (code "95") (name "/STM_JTCK") (class "Default")
      (node (ref "R48") (pin "2") (pinfunction "2_2") (pintype "passive"))
      (node (ref "U1") (pin "37") (pinfunction "PA14_37") (pintype "passive"))
    )
    (net (code "96") (name "/STM_JTMS") (class "Default")
      (node (ref "R50") (pin "2") (pinfunction "2_2") (pintype "passive"))
      (node (ref "U1") (pin "34") (pinfunction "PA13_34") (pintype "passive"))
    )
    (net (code "97") (name "/STM_RST") (class "Default")
      (node (ref "R13") (pin "2") (pinfunction "2_2") (pintype "passive"))
      (node (ref "U1") (pin "7") (pinfunction "NRST_7") (pintype "passive"))
    )
    (net (code "98") (name "/SWIM") (class "Default")
      (node (ref "U1") (pin "22") (pinfunction "PB11_22") (pintype "passive"))
      (node (ref "U1") (pin "45") (pinfunction "PB8_45") (pintype "passive"))
    )
    (net (code "99") (name "/SWIM_IN") (class "Default")
      (node (ref "U1") (pin "21") (pinfunction "PB10_21") (pintype "passive"))
      (node (ref "U1") (pin "43") (pinfunction "PB7_43") (pintype "passive"))
      (node (ref "U1") (pin "46") (pinfunction "PB9_46") (pintype "passive"))
    )
    (net (code "100") (name "/T_JTCK") (class "Default")
      (node (ref "R17") (pin "2") (pinfunction "2_2") (pintype "passive"))
      (node (ref "R51") (pin "2") (pinfunction "2_2") (pintype "passive"))
      (node (ref "U1") (pin "15") (pinfunction "PA5_15") (pintype "passive"))
      (node (ref "U1") (pin "26") (pinfunction "PB13_26") (pintype "passive"))
    )
    (net (code "101") (name "/T_JTMS") (class "Default")
      (node (ref "R12") (pin "1") (pinfunction "1_1") (pintype "passive"))
      (node (ref "R18") (pin "2") (pinfunction "2_2") (pintype "passive"))
      (node (ref "R19") (pin "1") (pinfunction "1_1") (pintype "passive"))
      (node (ref "U1") (pin "27") (pinfunction "PB14_27") (pintype "passive"))
    )
    (net (code "102") (name "/T_NRST") (class "Default")
      (node (ref "R20") (pin "2") (pinfunction "2_2") (pintype "passive"))
      (node (ref "R21") (pin "1") (pinfunction "1_1") (pintype "passive"))
      (node (ref "U1") (pin "18") (pinfunction "PB0_18") (pintype "passive"))
    )
    (net (code "103") (name "/T_SWDIO_IN") (class "Default")
      (node (ref "R12") (pin "2") (pinfunction "2_2") (pintype "passive"))
      (node (ref "U1") (pin "25") (pinfunction "PB12_25") (pintype "passive"))
    )
    (net (code "104") (name "/T_SWO") (class "Default")
      (node (ref "R22") (pin "2") (pinfunction "2_2") (pintype "passive"))
      (node (ref "R23") (pin "1") (pinfunction "1_1") (pintype "passive"))
      (node (ref "U1") (pin "31") (pinfunction "PA10_31") (pintype "passive"))
    )
    (net (code "105") (name "/USB_N") (class "Default")
      (node (ref "R8") (pin "2") (pinfunction "2_2") (pintype "passive"))
      (node (ref "U1") (pin "32") (pinfunction "PA11_32") (pintype "passive"))
    )
    (net (code "106") (name "/USB_P") (class "Default")
      (node (ref "R10") (pin "2") (pinfunction "2_2") (pintype "passive"))
      (node (ref "U1") (pin "33") (pinfunction "PA12_33") (pintype "passive"))
    )
    (net (code "107") (name "3V") (class "Default")
      (node (ref "C10") (pin "2") (pinfunction "2_2") (pintype "passive"))
      (node (ref "C7") (pin "2") (pinfunction "2_2") (pintype "passive"))
      (node (ref "C8") (pin "2") (pinfunction "2_2") (pintype "passive"))
      (node (ref "C9") (pin "2") (pinfunction "2_2") (pintype "passive"))
      (node (ref "D2") (pin "C") (pinfunction "C_C") (pintype "passive"))
      (node (ref "R2") (pin "1") (pinfunction "1_1") (pintype "passive"))
      (node (ref "R47") (pin "2") (pinfunction "2_2") (pintype "passive"))
      (node (ref "R6") (pin "1") (pinfunction "1_1") (pintype "passive"))
      (node (ref "U1") (pin "1") (pinfunction "VBAT_1") (pintype "passive"))
      (node (ref "U1") (pin "24") (pinfunction "VDD_1_24") (pintype "passive"))
      (node (ref "U1") (pin "36") (pinfunction "VDD_2_36") (pintype "passive"))
      (node (ref "U1") (pin "48") (pinfunction "VDD_3_48") (pintype "passive"))
      (node (ref "U1") (pin "9") (pinfunction "VDDA_9") (pintype "passive"))
    )
    (net (code "108") (name "5V") (class "Default")
      (node (ref "C5") (pin "2") (pinfunction "2_2") (pintype "passive"))
      (node (ref "C6") (pin "2") (pinfunction "2_2") (pintype "passive"))
      (node (ref "D1") (pin "C") (pinfunction "C_C") (pintype "passive"))
      (node (ref "U2") (pin "1") (pinfunction "VIN_1") (pintype "input"))
      (node (ref "U2") (pin "3") (pinfunction "VINH_3") (pintype "input"))
    )
    (net (code "109") (name "GND") (class "Default")
      (node (ref "C1") (pin "1") (pinfunction "1_1") (pintype "passive"))
      (node (ref "C10") (pin "1") (pinfunction "1_1") (pintype "passive"))
      (node (ref "C11") (pin "1") (pinfunction "1_1") (pintype "passive"))
      (node (ref "C12") (pin "1") (pinfunction "1_1") (pintype "passive"))
      (node (ref "C13") (pin "1") (pinfunction "1_1") (pintype "passive"))
      (node (ref "C14") (pin "2") (pinfunction "2_2") (pintype "passive"))
      (node (ref "C15") (pin "1") (pinfunction "1_1") (pintype "passive"))
      (node (ref "C16") (pin "2") (pinfunction "2_2") (pintype "passive"))
      (node (ref "C17") (pin "2") (pinfunction "2_2") (pintype "passive"))
      (node (ref "C18") (pin "1") (pinfunction "1_1") (pintype "passive"))
      (node (ref "C19") (pin "1") (pinfunction "1_1") (pintype "passive"))
      (node (ref "C2") (pin "1") (pinfunction "1_1") (pintype "passive"))
      (node (ref "C20") (pin "1") (pinfunction "1_1") (pintype "passive"))
      (node (ref "C21") (pin "1") (pinfunction "1_1") (pintype "passive"))
      (node (ref "C22") (pin "1") (pinfunction "1_1") (pintype "passive"))
      (node (ref "C23") (pin "1") (pinfunction "1_1") (pintype "passive"))
      (node (ref "C24") (pin "1") (pinfunction "1_1") (pintype "passive"))
      (node (ref "C25") (pin "1") (pinfunction "1_1") (pintype "passive"))
      (node (ref "C26") (pin "1") (pinfunction "1_1") (pintype "passive"))
      (node (ref "C27") (pin "1") (pinfunction "1_1") (pintype "passive"))
      (node (ref "C3") (pin "1") (pinfunction "1_1") (pintype "passive"))
      (node (ref "C4") (pin "1") (pinfunction "1_1") (pintype "passive"))
      (node (ref "C5") (pin "1") (pinfunction "1_1") (pintype "passive"))
      (node (ref "C6") (pin "1") (pinfunction "1_1") (pintype "passive"))
      (node (ref "C7") (pin "1") (pinfunction "1_1") (pintype "passive"))
      (node (ref "C8") (pin "1") (pinfunction "1_1") (pintype "passive"))
      (node (ref "C9") (pin "1") (pinfunction "1_1") (pintype "passive"))
      (node (ref "CN1") (pin "5") (pinfunction "GND_5") (pintype "passive"))
      (node (ref "CN1") (pin "S") (pinfunction "Shield_S") (pintype "passive"))
      (node (ref "J1") (pin "3") (pinfunction "3_3") (pintype "passive"))
      (node (ref "LED1") (pin "1") (pinfunction "K_RED_1") (pintype "passive"))
      (node (ref "R1") (pin "2") (pinfunction "2_2") (pintype "passive"))
      (node (ref "R14") (pin "1") (pinfunction "1_1") (pintype "passive"))
      (node (ref "R15") (pin "2") (pinfunction "2_2") (pintype "passive"))
      (node (ref "R25") (pin "2") (pinfunction "2_2") (pintype "passive"))
      (node (ref "R4") (pin "2") (pinfunction "2_2") (pintype "passive"))
      (node (ref "R49") (pin "2") (pinfunction "2_2") (pintype "passive"))
      (node (ref "R7") (pin "2") (pinfunction "2_2") (pintype "passive"))
      (node (ref "R9") (pin "2") (pinfunction "2_2") (pintype "passive"))
      (node (ref "U1") (pin "20") (pinfunction "PB2_20") (pintype "passive"))
      (node (ref "U1") (pin "23") (pinfunction "VSS_1_23") (pintype "passive"))
      (node (ref "U1") (pin "35") (pinfunction "VSS_2_35") (pintype "passive"))
      (node (ref "U1") (pin "47") (pinfunction "VSS_3_47") (pintype "passive"))
      (node (ref "U1") (pin "8") (pinfunction "VSSA_8") (pintype "passive"))
      (node (ref "U2") (pin "2") (pinfunction "GND_2") (pintype "power_in"))
      (node (ref "U3") (pin "20") (pinfunction "VSSA/VREF-_20") (pintype "passive"))
      (node (ref "U3") (pin "49") (pinfunction "VSS_1_49") (pintype "passive"))
      (node (ref "U3") (pin "74") (pinfunction "VSS_2_74") (pintype "passive"))
      (node (ref "U3") (pin "99") (pinfunction "VSS_3_99") (pintype "passive"))
    )
    (net (code "110") (name "Net-(C13-Pad2)") (class "Default")
      (node (ref "C13") (pin "2") (pinfunction "2_2") (pintype "passive"))
      (node (ref "R13") (pin "1") (pinfunction "1_1") (pintype "passive"))
    )
    (net (code "111") (name "Net-(CN1-D+)") (class "Default")
      (node (ref "CN1") (pin "3") (pinfunction "D+_3") (pintype "passive"))
      (node (ref "R10") (pin "1") (pinfunction "1_1") (pintype "passive"))
    )
    (net (code "112") (name "Net-(CN1-D-)") (class "Default")
      (node (ref "CN1") (pin "2") (pinfunction "D-_2") (pintype "passive"))
      (node (ref "R8") (pin "1") (pinfunction "1_1") (pintype "passive"))
    )
    (net (code "113") (name "Net-(CN1-ID)") (class "Default")
      (node (ref "CN1") (pin "4") (pinfunction "ID_4") (pintype "passive"))
      (node (ref "R9") (pin "1") (pinfunction "1_1") (pintype "passive"))
    )
    (net (code "114") (name "Net-(CN1-VCC)") (class "Default")
      (node (ref "CN1") (pin "1") (pinfunction "VCC_1") (pintype "passive"))
      (node (ref "D1") (pin "A") (pinfunction "A_A") (pintype "passive"))
    )
    (net (code "115") (name "Net-(D3-PadA)") (class "Default")
      (node (ref "D3") (pin "A") (pinfunction "A_A") (pintype "passive"))
      (node (ref "J1") (pin "1") (pinfunction "1_1") (pintype "passive"))
      (node (ref "R15") (pin "1") (pinfunction "1_1") (pintype "passive"))
    )
    (net (code "116") (name "Net-(D3-PadC)") (class "Default")
      (node (ref "D3") (pin "C") (pinfunction "C_C") (pintype "passive"))
      (node (ref "R16") (pin "1") (pinfunction "1_1") (pintype "passive"))
    )
    (net (code "117") (name "Net-(J1-Pad2)") (class "Default")
      (node (ref "J1") (pin "2") (pinfunction "2_2") (pintype "passive"))
      (node (ref "R17") (pin "1") (pinfunction "1_1") (pintype "passive"))
    )
    (net (code "118") (name "Net-(J1-Pad4)") (class "Default")
      (node (ref "J1") (pin "4") (pinfunction "4_4") (pintype "passive"))
      (node (ref "R18") (pin "1") (pinfunction "1_1") (pintype "passive"))
    )
    (net (code "119") (name "Net-(J1-Pad5)") (class "Default")
      (node (ref "J1") (pin "5") (pinfunction "5_5") (pintype "passive"))
      (node (ref "R20") (pin "1") (pinfunction "1_1") (pintype "passive"))
    )
    (net (code "120") (name "Net-(J1-Pad6)") (class "Default")
      (node (ref "J1") (pin "6") (pinfunction "6_6") (pintype "passive"))
      (node (ref "R22") (pin "1") (pinfunction "1_1") (pintype "passive"))
    )
    (net (code "121") (name "Net-(J2-Pad1)") (class "Default")
      (node (ref "J2") (pin "1") (pinfunction "1_1") (pintype "passive"))
      (node (ref "R47") (pin "1") (pinfunction "1_1") (pintype "passive"))
      (node (ref "R51") (pin "1") (pinfunction "1_1") (pintype "passive"))
    )
    (net (code "122") (name "Net-(J2-Pad2)") (class "Default")
      (node (ref "J2") (pin "2") (pinfunction "2_2") (pintype "passive"))
      (node (ref "R46") (pin "1") (pinfunction "1_1") (pintype "passive"))
      (node (ref "R48") (pin "1") (pinfunction "1_1") (pintype "passive"))
    )
    (net (code "123") (name "Net-(J2-Pad3)") (class "Default")
      (node (ref "J2") (pin "3") (pinfunction "3_3") (pintype "passive"))
      (node (ref "R19") (pin "2") (pinfunction "2_2") (pintype "passive"))
      (node (ref "R49") (pin "1") (pinfunction "1_1") (pintype "passive"))
    )
    (net (code "124") (name "Net-(J2-Pad4)") (class "Default")
      (node (ref "J2") (pin "4") (pinfunction "4_4") (pintype "passive"))
      (node (ref "R45") (pin "1") (pinfunction "1_1") (pintype "passive"))
      (node (ref "R50") (pin "1") (pinfunction "1_1") (pintype "passive"))
    )
    (net (code "125") (name "Net-(LED1-A_GREEN)") (class "Default")
      (node (ref "LED1") (pin "4") (pinfunction "A_GREEN_4") (pintype "passive"))
      (node (ref "R2") (pin "2") (pinfunction "2_2") (pintype "passive"))
    )
    (net (code "126") (name "Net-(LED1-A_RED)") (class "Default")
      (node (ref "LED1") (pin "2") (pinfunction "A_RED_2") (pintype "passive"))
      (node (ref "R5") (pin "2") (pinfunction "2_2") (pintype "passive"))
    )
    (net (code "127") (name "Net-(LED1-K_GREEN)") (class "Default")
      (node (ref "LED1") (pin "3") (pinfunction "K_GREEN_3") (pintype "passive"))
      (node (ref "R3") (pin "1") (pinfunction "1_1") (pintype "passive"))
    )
    (net (code "128") (name "Net-(U1-BOOT0)") (class "Default")
      (node (ref "R14") (pin "2") (pinfunction "2_2") (pintype "passive"))
      (node (ref "U1") (pin "44") (pinfunction "BOOT0_44") (pintype "passive"))
    )
    (net (code "129") (name "Net-(U1-PA8)") (class "Default")
      (node (ref "R11") (pin "1") (pinfunction "1_1") (pintype "passive"))
      (node (ref "U1") (pin "29") (pinfunction "PA8_29") (pintype "passive"))
    )
    (net (code "130") (name "Net-(U1-PC13-TAMPER-RTC)") (class "Default")
      (node (ref "R1") (pin "1") (pinfunction "1_1") (pintype "passive"))
      (node (ref "U1") (pin "2") (pinfunction "PC13-TAMPER-RTC_2") (pintype "passive"))
    )
    (net (code "131") (name "Net-(U1-PC14-OSC32_IN)") (class "Default")
      (node (ref "R4") (pin "1") (pinfunction "1_1") (pintype "passive"))
      (node (ref "U1") (pin "3") (pinfunction "PC14-OSC32_IN_3") (pintype "passive"))
    )
    (net (code "132") (name "Net-(U2-BYPASS)") (class "Default")
      (node (ref "C4") (pin "2") (pinfunction "2_2") (pintype "passive"))
      (node (ref "U2") (pin "4") (pinfunction "BYPASS_4") (pintype "passive"))
    )
    (net (code "133") (name "Net-(U2-VOUT)") (class "Default")
      (node (ref "C2") (pin "2") (pinfunction "2_2") (pintype "passive"))
      (node (ref "C3") (pin "2") (pinfunction "2_2") (pintype "passive"))
      (node (ref "D2") (pin "A") (pinfunction "A_A") (pintype "passive"))
      (node (ref "U2") (pin "5") (pinfunction "VOUT_5") (pintype "output"))
    )
    (net (code "134") (name "Net-(U3-VBAT)") (class "Default")
      (node (ref "C25") (pin "2") (pinfunction "2_2") (pintype "passive"))
      (node (ref "R24") (pin "1") (pinfunction "1_1") (pintype "passive"))
      (node (ref "U3") (pin "6") (pinfunction "VBAT_6") (pintype "passive"))
    )
    (net (code "135") (name "Net-(U3-VREF+)") (class "Default")
      (node (ref "C16") (pin "1") (pinfunction "1_1") (pintype "passive"))
      (node (ref "C17") (pin "1") (pinfunction "1_1") (pintype "passive"))
      (node (ref "U3") (pin "21") (pinfunction "VREF+_21") (pintype "passive"))
    )
    (net (code "136") (name "VDD") (class "Default")
      (node (ref "C14") (pin "1") (pinfunction "1_1") (pintype "passive"))
      (node (ref "C15") (pin "2") (pinfunction "2_2") (pintype "passive"))
      (node (ref "C18") (pin "2") (pinfunction "2_2") (pintype "passive"))
      (node (ref "C19") (pin "2") (pinfunction "2_2") (pintype "passive"))
      (node (ref "C20") (pin "2") (pinfunction "2_2") (pintype "passive"))
      (node (ref "C21") (pin "2") (pinfunction "2_2") (pintype "passive"))
      (node (ref "C22") (pin "2") (pinfunction "2_2") (pintype "passive"))
      (node (ref "C23") (pin "2") (pinfunction "2_2") (pintype "passive"))
      (node (ref "C24") (pin "2") (pinfunction "2_2") (pintype "passive"))
      (node (ref "R24") (pin "2") (pinfunction "2_2") (pintype "passive"))
      (node (ref "U3") (pin "100") (pinfunction "VDD_4_100") (pintype "passive"))
      (node (ref "U3") (pin "22") (pinfunction "VDDA_22") (pintype "passive"))
      (node (ref "U3") (pin "28") (pinfunction "VDD_1_28") (pintype "passive"))
      (node (ref "U3") (pin "50") (pinfunction "VDD_2_50") (pintype "passive"))
      (node (ref "U3") (pin "75") (pinfunction "VDD_3_75") (pintype "passive"))
    )
    (net (code "137") (name "unconnected-(U1-PA1-Pad11)") (class "Default")
      (node (ref "U1") (pin "11") (pinfunction "PA1_11") (pintype "passive+no_connect"))
    )
    (net (code "138") (name "unconnected-(U1-PA4-Pad14)") (class "Default")
      (node (ref "U1") (pin "14") (pinfunction "PA4_14") (pintype "passive+no_connect"))
    )
    (net (code "139") (name "unconnected-(U1-PA6-Pad16)") (class "Default")
      (node (ref "U1") (pin "16") (pinfunction "PA6_16") (pintype "passive+no_connect"))
    )
    (net (code "140") (name "unconnected-(U1-PA7-Pad17)") (class "Default")
      (node (ref "U1") (pin "17") (pinfunction "PA7_17") (pintype "passive+no_connect"))
    )
    (net (code "141") (name "unconnected-(U1-PA15-Pad38)") (class "Default")
      (node (ref "U1") (pin "38") (pinfunction "PA15_38") (pintype "passive+no_connect"))
    )
    (net (code "142") (name "unconnected-(U1-PB1-Pad19)") (class "Default")
      (node (ref "U1") (pin "19") (pinfunction "PB1_19") (pintype "passive+no_connect"))
    )
    (net (code "143") (name "unconnected-(U1-PB3-Pad39)") (class "Default")
      (node (ref "U1") (pin "39") (pinfunction "PB3_39") (pintype "passive+no_connect"))
    )
    (net (code "144") (name "unconnected-(U1-PB4-Pad40)") (class "Default")
      (node (ref "U1") (pin "40") (pinfunction "PB4_40") (pintype "passive+no_connect"))
    )
    (net (code "145") (name "unconnected-(U1-PB5-Pad41)") (class "Default")
      (node (ref "U1") (pin "41") (pinfunction "PB5_41") (pintype "passive+no_connect"))
    )
    (net (code "146") (name "unconnected-(U1-PB6-Pad42)") (class "Default")
      (node (ref "U1") (pin "42") (pinfunction "PB6_42") (pintype "passive+no_connect"))
    )
    (net (code "147") (name "unconnected-(U1-PB15-Pad28)") (class "Default")
      (node (ref "U1") (pin "28") (pinfunction "PB15_28") (pintype "passive+no_connect"))
    )
    (net (code "148") (name "unconnected-(U1-PC15-OSC32_OUT-Pad4)") (class "Default")
      (node (ref "U1") (pin "4") (pinfunction "PC15-OSC32_OUT_4") (pintype "passive+no_connect"))
    )
    (net (code "149") (name "unconnected-(U3-PF0{slash}OSC_IN-Pad12)") (class "Default")
      (node (ref "U3") (pin "12") (pinfunction "PF0/OSC_IN_12") (pintype "passive+no_connect"))
    )
    (net (code "150") (name "unconnected-(U3-PF1{slash}OSC_OUT-Pad13)") (class "Default")
      (node (ref "U3") (pin "13") (pinfunction "PF1/OSC_OUT_13") (pintype "passive+no_connect"))
    )
  )
)
